# Power.net
KiCad netlist of a schematic drawn in Altium Designer
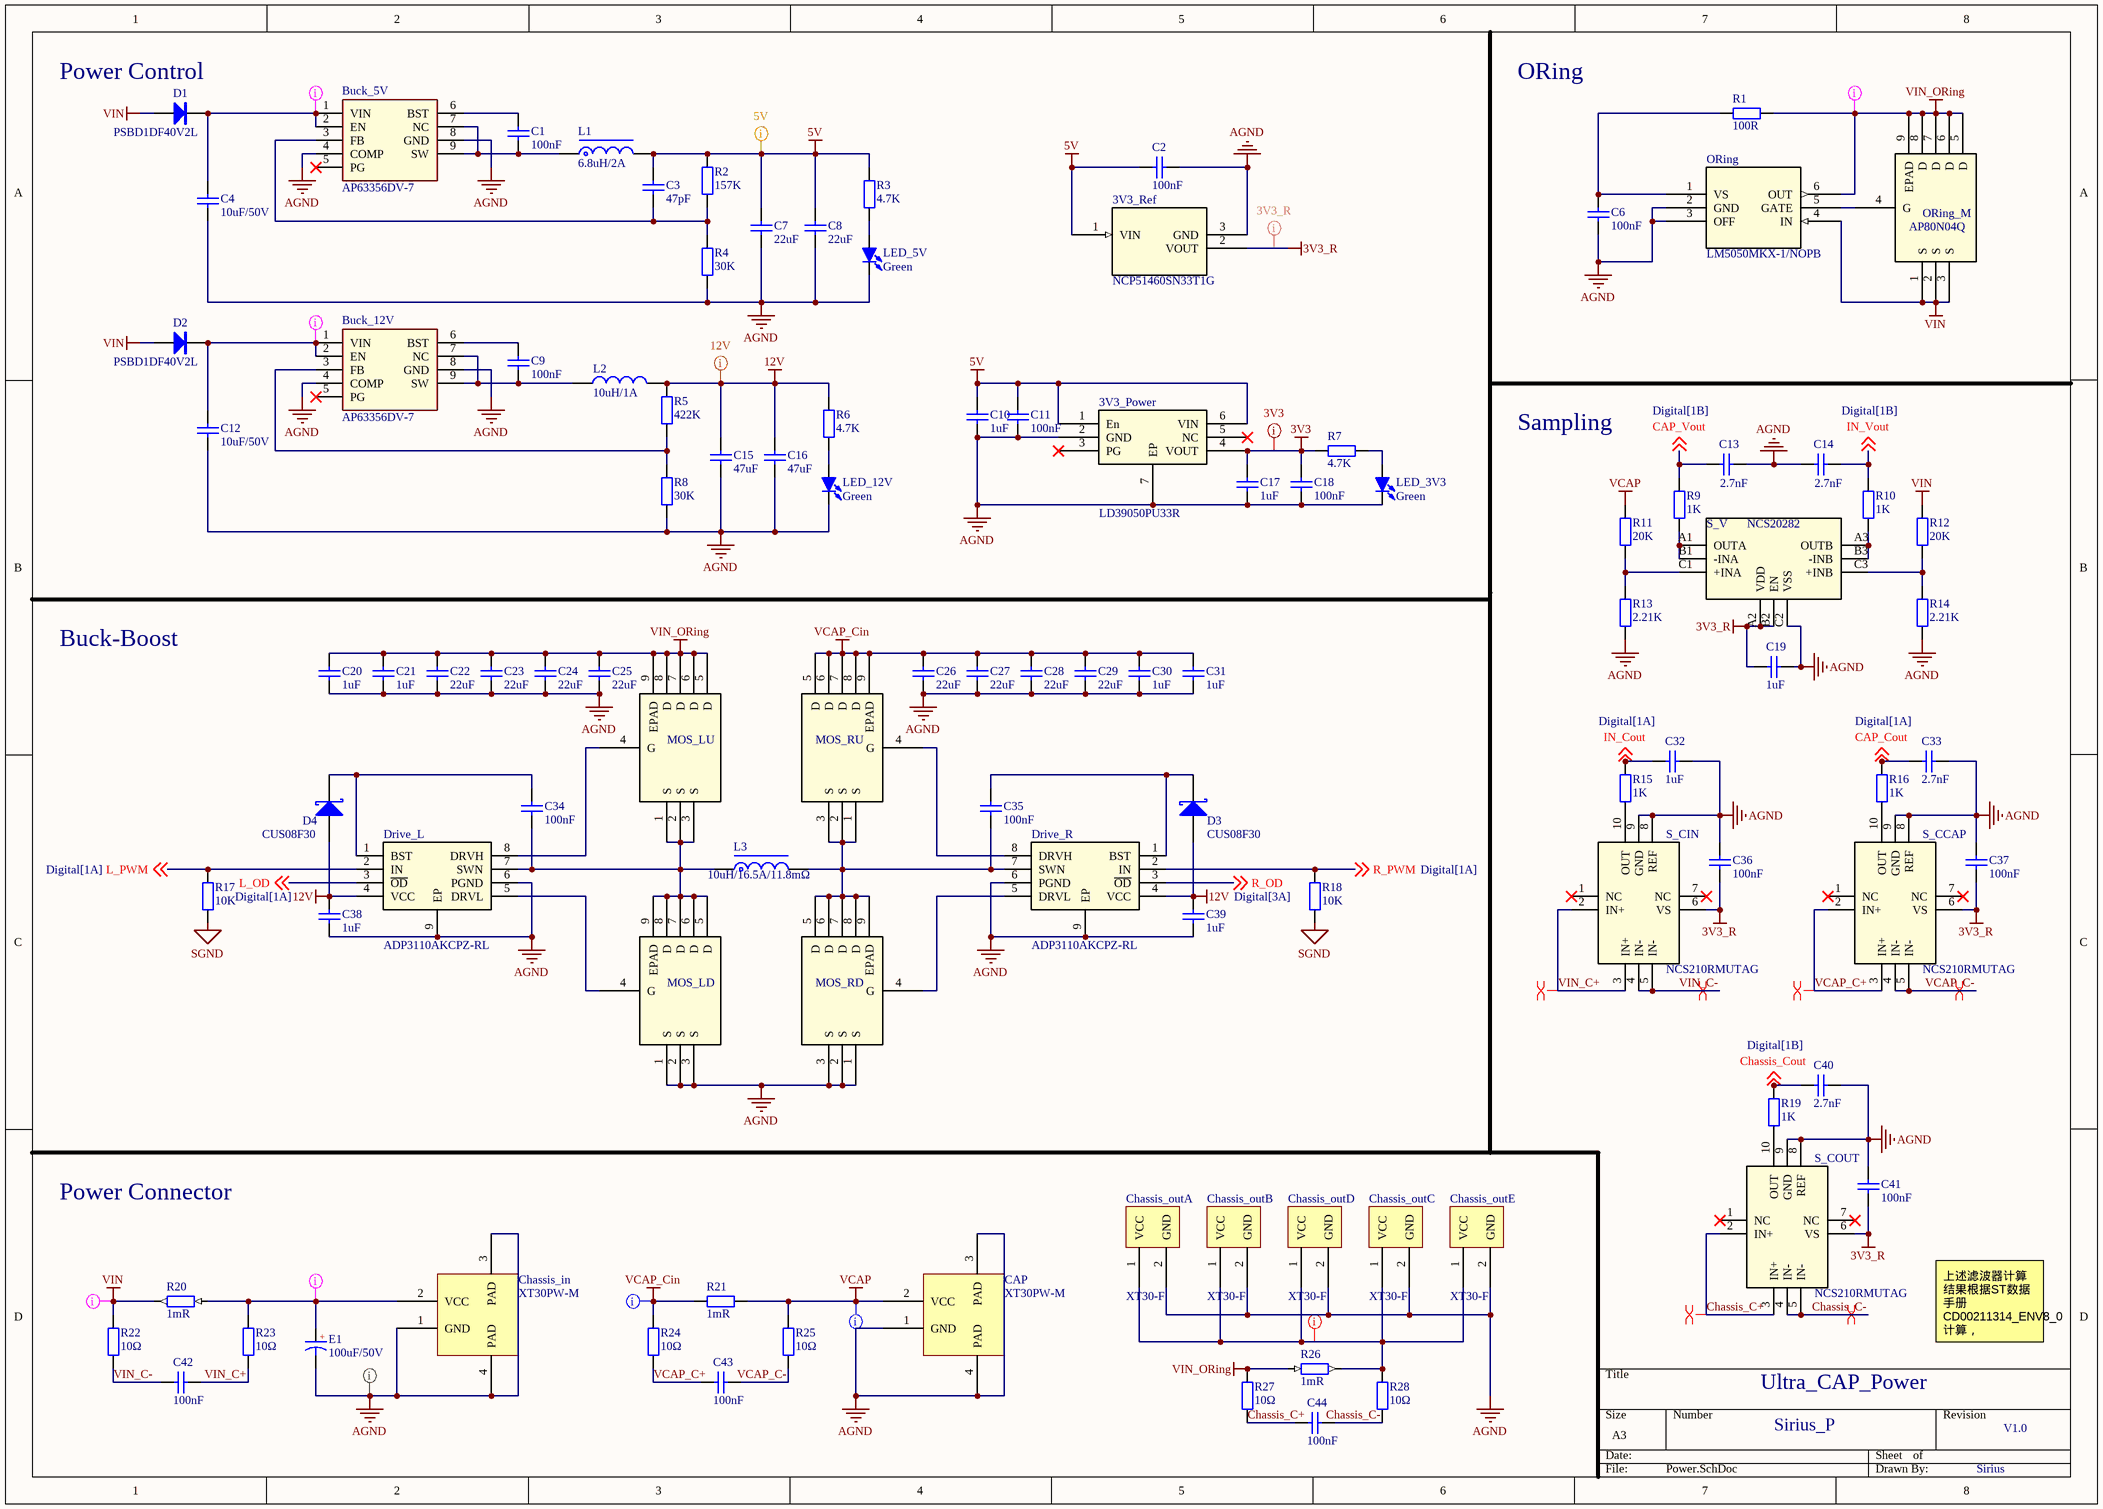
[diagram p0: Power.SchDoc]

(export (version "E")
  (design (tool "Eeschema 10.0.6"))
  (components
    (comp (ref "3V3_Power")
      (value "LD39050PU33R")
      (footprint "SON_DFN6_3X3_STM-L")
      (description "LDO-3V3/500mA")
      (libsource (lib "Extra Sch") (part "LD39050PU33R"))
    )
    (comp (ref "3V3_Ref")
      (value "NCP51460SN33T1G")
      (footprint "SOT23")
      (description "基准电压源3V3")
      (fields (field (name "COPYRIGHT") "Copyright (C) 2022 Ultra Librarian. All rights reserved."))
      (libsource (lib "Extra Sch") (part "NCP51460SN33T1G"))
    )
    (comp (ref "Buck_5V")
      (value "AP63356DV-7")
      (footprint "AP63356DV7")
      (fields (field (name "MOUSER PART NUMBER") "621-AP63356DV-7"))
      (libsource (lib "Extra Sch") (part "AP63356DV-7"))
    )
    (comp (ref "Buck_12V")
      (value "AP63356DV-7")
      (footprint "AP63356DV7")
      (fields (field (name "MOUSER PART NUMBER") "621-AP63356DV-7"))
      (libsource (lib "Extra Sch") (part "AP63356DV-7"))
    )
    (comp (ref "C1")
      (value "100nF")
      (footprint "C0603_L")
      (description "贴片电容")
      (libsource (lib "0.1 - 电阻-电容-电感-晶振-晶体-磁珠-电位器") (part "C"))
    )
    (comp (ref "C2")
      (value "100nF")
      (footprint "C0603_L")
      (description "贴片电容")
      (libsource (lib "0.1 - 电阻-电容-电感-晶振-晶体-磁珠-电位器") (part "C"))
    )
    (comp (ref "C3")
      (value "47pF")
      (footprint "C0603_L")
      (description "贴片电容")
      (libsource (lib "0.1 - 电阻-电容-电感-晶振-晶体-磁珠-电位器") (part "C"))
    )
    (comp (ref "C4")
      (value "10uF/50V")
      (footprint "C0603_L")
      (description "贴片电容")
      (libsource (lib "0.1 - 电阻-电容-电感-晶振-晶体-磁珠-电位器") (part "C"))
    )
    (comp (ref "C6")
      (value "100nF")
      (footprint "C0603_L")
      (description "贴片电容")
      (libsource (lib "0.1 - 电阻-电容-电感-晶振-晶体-磁珠-电位器") (part "C"))
    )
    (comp (ref "C7")
      (value "22uF")
      (footprint "C1210_L")
      (description "贴片电容")
      (libsource (lib "0.1 - 电阻-电容-电感-晶振-晶体-磁珠-电位器") (part "C"))
    )
    (comp (ref "C8")
      (value "22uF")
      (footprint "C1210_L")
      (description "贴片电容")
      (libsource (lib "0.1 - 电阻-电容-电感-晶振-晶体-磁珠-电位器") (part "C"))
    )
    (comp (ref "C9")
      (value "100nF")
      (footprint "C0603_L")
      (description "贴片电容")
      (libsource (lib "0.1 - 电阻-电容-电感-晶振-晶体-磁珠-电位器") (part "C"))
    )
    (comp (ref "C10")
      (value "1uF")
      (footprint "C0603_L")
      (description "贴片电容")
      (libsource (lib "0.1 - 电阻-电容-电感-晶振-晶体-磁珠-电位器") (part "C"))
    )
    (comp (ref "C11")
      (value "100nF")
      (footprint "C0603_L")
      (description "贴片电容")
      (libsource (lib "0.1 - 电阻-电容-电感-晶振-晶体-磁珠-电位器") (part "C"))
    )
    (comp (ref "C12")
      (value "10uF/50V")
      (footprint "C0603_L")
      (description "贴片电容")
      (libsource (lib "0.1 - 电阻-电容-电感-晶振-晶体-磁珠-电位器") (part "C"))
    )
    (comp (ref "C13")
      (value "2.7nF")
      (footprint "C0603_L")
      (description "贴片电容")
      (libsource (lib "0.1 - 电阻-电容-电感-晶振-晶体-磁珠-电位器") (part "C"))
    )
    (comp (ref "C14")
      (value "2.7nF")
      (footprint "C0603_L")
      (description "贴片电容")
      (libsource (lib "0.1 - 电阻-电容-电感-晶振-晶体-磁珠-电位器") (part "C"))
    )
    (comp (ref "C15")
      (value "47uF")
      (footprint "C1206_L")
      (description "贴片电容")
      (libsource (lib "0.1 - 电阻-电容-电感-晶振-晶体-磁珠-电位器") (part "C"))
    )
    (comp (ref "C16")
      (value "47uF")
      (footprint "C1206_L")
      (description "贴片电容")
      (libsource (lib "0.1 - 电阻-电容-电感-晶振-晶体-磁珠-电位器") (part "C"))
    )
    (comp (ref "C17")
      (value "1uF")
      (footprint "C0603_L")
      (description "贴片电容")
      (libsource (lib "0.1 - 电阻-电容-电感-晶振-晶体-磁珠-电位器") (part "C"))
    )
    (comp (ref "C18")
      (value "100nF")
      (footprint "C0603_L")
      (description "贴片电容")
      (libsource (lib "0.1 - 电阻-电容-电感-晶振-晶体-磁珠-电位器") (part "C"))
    )
    (comp (ref "C19")
      (value "1uF")
      (footprint "C0603_L")
      (description "贴片电容")
      (libsource (lib "0.1 - 电阻-电容-电感-晶振-晶体-磁珠-电位器") (part "C"))
    )
    (comp (ref "C20")
      (value "1uF")
      (footprint "C0603_L")
      (description "贴片电容")
      (libsource (lib "0.1 - 电阻-电容-电感-晶振-晶体-磁珠-电位器") (part "C"))
    )
    (comp (ref "C21")
      (value "1uF")
      (footprint "C0603_L")
      (description "贴片电容")
      (libsource (lib "0.1 - 电阻-电容-电感-晶振-晶体-磁珠-电位器") (part "C"))
    )
    (comp (ref "C22")
      (value "22uF")
      (footprint "C2220_no overlay")
      (description "贴片电容")
      (libsource (lib "0.1 - 电阻-电容-电感-晶振-晶体-磁珠-电位器") (part "C"))
    )
    (comp (ref "C23")
      (value "22uF")
      (footprint "C2220_no overlay")
      (description "贴片电容")
      (libsource (lib "0.1 - 电阻-电容-电感-晶振-晶体-磁珠-电位器") (part "C"))
    )
    (comp (ref "C24")
      (value "22uF")
      (footprint "C2220_no overlay")
      (description "贴片电容")
      (libsource (lib "0.1 - 电阻-电容-电感-晶振-晶体-磁珠-电位器") (part "C"))
    )
    (comp (ref "C25")
      (value "22uF")
      (footprint "C2220_no overlay")
      (description "贴片电容")
      (libsource (lib "0.1 - 电阻-电容-电感-晶振-晶体-磁珠-电位器") (part "C"))
    )
    (comp (ref "C26")
      (value "22uF")
      (footprint "C2220_no overlay")
      (description "贴片电容")
      (libsource (lib "0.1 - 电阻-电容-电感-晶振-晶体-磁珠-电位器") (part "C"))
    )
    (comp (ref "C27")
      (value "22uF")
      (footprint "C2220_no overlay")
      (description "贴片电容")
      (libsource (lib "0.1 - 电阻-电容-电感-晶振-晶体-磁珠-电位器") (part "C"))
    )
    (comp (ref "C28")
      (value "22uF")
      (footprint "C2220_no overlay")
      (description "贴片电容")
      (libsource (lib "0.1 - 电阻-电容-电感-晶振-晶体-磁珠-电位器") (part "C"))
    )
    (comp (ref "C29")
      (value "22uF")
      (footprint "C2220_no overlay")
      (description "贴片电容")
      (libsource (lib "0.1 - 电阻-电容-电感-晶振-晶体-磁珠-电位器") (part "C"))
    )
    (comp (ref "C30")
      (value "1uF")
      (footprint "C0603_L")
      (description "贴片电容")
      (libsource (lib "0.1 - 电阻-电容-电感-晶振-晶体-磁珠-电位器") (part "C"))
    )
    (comp (ref "C31")
      (value "1uF")
      (footprint "C0603_L")
      (description "贴片电容")
      (libsource (lib "0.1 - 电阻-电容-电感-晶振-晶体-磁珠-电位器") (part "C"))
    )
    (comp (ref "C32")
      (value "1uF")
      (footprint "C0603_L")
      (description "贴片电容")
      (libsource (lib "0.1 - 电阻-电容-电感-晶振-晶体-磁珠-电位器") (part "C"))
    )
    (comp (ref "C33")
      (value "2.7nF")
      (footprint "C0603_L")
      (description "贴片电容")
      (libsource (lib "0.1 - 电阻-电容-电感-晶振-晶体-磁珠-电位器") (part "C"))
    )
    (comp (ref "C34")
      (value "100nF")
      (footprint "C0603_L")
      (description "贴片电容")
      (libsource (lib "0.1 - 电阻-电容-电感-晶振-晶体-磁珠-电位器") (part "C"))
    )
    (comp (ref "C35")
      (value "100nF")
      (footprint "C0603_L")
      (description "贴片电容")
      (libsource (lib "0.1 - 电阻-电容-电感-晶振-晶体-磁珠-电位器") (part "C"))
    )
    (comp (ref "C36")
      (value "100nF")
      (footprint "C0603_L")
      (description "贴片电容")
      (libsource (lib "0.1 - 电阻-电容-电感-晶振-晶体-磁珠-电位器") (part "C"))
    )
    (comp (ref "C37")
      (value "100nF")
      (footprint "C0603_L")
      (description "贴片电容")
      (libsource (lib "0.1 - 电阻-电容-电感-晶振-晶体-磁珠-电位器") (part "C"))
    )
    (comp (ref "C38")
      (value "1uF")
      (footprint "C0603_L")
      (description "贴片电容")
      (libsource (lib "0.1 - 电阻-电容-电感-晶振-晶体-磁珠-电位器") (part "C"))
    )
    (comp (ref "C39")
      (value "1uF")
      (footprint "C0603_L")
      (description "贴片电容")
      (libsource (lib "0.1 - 电阻-电容-电感-晶振-晶体-磁珠-电位器") (part "C"))
    )
    (comp (ref "C40")
      (value "2.7nF")
      (footprint "C0603_L")
      (description "贴片电容")
      (libsource (lib "0.1 - 电阻-电容-电感-晶振-晶体-磁珠-电位器") (part "C"))
    )
    (comp (ref "C41")
      (value "100nF")
      (footprint "C0603_L")
      (description "贴片电容")
      (libsource (lib "0.1 - 电阻-电容-电感-晶振-晶体-磁珠-电位器") (part "C"))
    )
    (comp (ref "C42")
      (value "100nF")
      (footprint "C0603_L")
      (description "贴片电容")
      (libsource (lib "0.1 - 电阻-电容-电感-晶振-晶体-磁珠-电位器") (part "C"))
    )
    (comp (ref "C43")
      (value "100nF")
      (footprint "C0603_L")
      (description "贴片电容")
      (libsource (lib "0.1 - 电阻-电容-电感-晶振-晶体-磁珠-电位器") (part "C"))
    )
    (comp (ref "C44")
      (value "100nF")
      (footprint "C0603_L")
      (description "贴片电容")
      (libsource (lib "0.1 - 电阻-电容-电感-晶振-晶体-磁珠-电位器") (part "C"))
    )
    (comp (ref "CAP")
      (value "XT30PW-M")
      (footprint "CONN-TH_XT30PW-M")
      (libsource (lib "Extra Sch") (part "XT30PW-M"))
    )
    (comp (ref "Chassis_in")
      (value "XT30PW-M")
      (footprint "CONN-TH_XT30PW-M")
      (libsource (lib "Extra Sch") (part "XT30PW-M"))
    )
    (comp (ref "Chassis_outA")
      (value "XT30-F")
      (footprint "XT30-F")
      (libsource (lib "Extra Sch") (part "XT30-F"))
    )
    (comp (ref "Chassis_outB")
      (value "XT30-F")
      (footprint "XT30-F")
      (libsource (lib "Extra Sch") (part "XT30-F"))
    )
    (comp (ref "Chassis_outC")
      (value "XT30-F")
      (footprint "XT30-F")
      (libsource (lib "Extra Sch") (part "XT30-F"))
    )
    (comp (ref "Chassis_outD")
      (value "XT30-F")
      (footprint "XT30-F")
      (libsource (lib "Extra Sch") (part "XT30-F"))
    )
    (comp (ref "Chassis_outE")
      (value "XT30-F")
      (footprint "XT30-F")
      (libsource (lib "Extra Sch") (part "XT30-F"))
    )
    (comp (ref "D1")
      (value "PSBD1DF40V2L")
      (footprint "SOD-123")
      (description "肖特基二极管")
      (libsource (lib "0.2 - 二极管-TVS-ESD-整流桥") (part "1N5822"))
    )
    (comp (ref "D2")
      (value "PSBD1DF40V2L")
      (footprint "SOD-123")
      (description "肖特基二极管")
      (libsource (lib "0.2 - 二极管-TVS-ESD-整流桥") (part "1N5822"))
    )
    (comp (ref "D3")
      (value "CUS08F30")
      (footprint "SOD-323")
      (description "肖特基二极管")
      (libsource (lib "0.2 - 二极管-TVS-ESD-整流桥") (part "1N5819"))
    )
    (comp (ref "D4")
      (value "CUS08F30")
      (footprint "SOD-323")
      (description "肖特基二极管")
      (libsource (lib "0.2 - 二极管-TVS-ESD-整流桥") (part "1N5819"))
    )
    (comp (ref "Drive_L")
      (value "ADP3110AKCPZ-RL")
      (footprint "SON50P300X300X100-9N")
      (fields (field (name "MOUSER PART NUMBER") "863-ADP3110AKCPZ-RL"))
      (libsource (lib "") (part "ADP3110AKCPZ-RL_1"))
    )
    (comp (ref "Drive_R")
      (value "ADP3110AKCPZ-RL")
      (footprint "SON50P300X300X100-9N")
      (fields (field (name "MOUSER PART NUMBER") "863-ADP3110AKCPZ-RL"))
      (libsource (lib "Extra Sch") (part "ADP3110AKCPZ-RL"))
    )
    (comp (ref "E1")
      (value "100uF/50V")
      (footprint "CT 3.5*8*8 - R")
      (description "直插固态电容")
      (libsource (lib "0.1 - 电阻-电容-电感-晶振-晶体-磁珠-电位器") (part "CS"))
    )
    (comp (ref "L1")
      (value "6.8uH/2A")
      (footprint "L-SMD-0420")
      (description "一体成型电感")
      (libsource (lib "0.1 - 电阻-电容-电感-晶振-晶体-磁珠-电位器") (part "L-Molding Choke"))
    )
    (comp (ref "L2")
      (value "10uH/1A")
      (footprint "L1210")
      (description "贴片小功率电感")
      (libsource (lib "0.1 - 电阻-电容-电感-晶振-晶体-磁珠-电位器") (part "L"))
    )
    (comp (ref "L3")
      (value "10uH/16.5A/11.8mΩ")
      (footprint "INDPM176169X700N")
      (description "一体成型电感\r\nTMPC1707HP-100MG-D")
      (libsource (lib "0.1 - 电阻-电容-电感-晶振-晶体-磁珠-电位器") (part "L-Molding Choke"))
    )
    (comp (ref "LED_3V3")
      (value "Green")
      (footprint "LED0603_G")
      (description "贴片LED")
      (libsource (lib "0.3 - LED发光二极管-IR二极管_接收管-光耦") (part "LED-SMD"))
    )
    (comp (ref "LED_5V")
      (value "Green")
      (footprint "LED0603_G")
      (description "贴片LED")
      (libsource (lib "0.3 - LED发光二极管-IR二极管_接收管-光耦") (part "LED-SMD"))
    )
    (comp (ref "LED_12V")
      (value "Green")
      (footprint "LED0603_G")
      (description "贴片LED")
      (libsource (lib "0.3 - LED发光二极管-IR二极管_接收管-光耦") (part "LED-SMD"))
    )
    (comp (ref "MOS_LD")
      (value "HYG025N06LS1C2")
      (footprint "PDFN5*6-8l")
      (description "NMOS 60V/170A")
      (fields
        (field (name "MANUFACTURER_PART_NUMBER") "AON7418")
        (field (name "COPYRIGHT") "Copyright (C) 2022 Ultra Librarian. All rights reserved.")
      )
      (libsource (lib "") (part "HYG025N06LS1C2_1"))
    )
    (comp (ref "MOS_LU")
      (value "HYG025N06LS1C2")
      (footprint "PDFN5*6-8l")
      (description "NMOS 60V/170A")
      (fields
        (field (name "MANUFACTURER_PART_NUMBER") "AON7418")
        (field (name "COPYRIGHT") "Copyright (C) 2022 Ultra Librarian. All rights reserved.")
      )
      (libsource (lib "") (part "HYG025N06LS1C2_1"))
    )
    (comp (ref "MOS_RD")
      (value "HYG025N06LS1C2")
      (footprint "PDFN5*6-8l")
      (description "NMOS 60V/170A")
      (fields
        (field (name "MANUFACTURER_PART_NUMBER") "AON7418")
        (field (name "COPYRIGHT") "Copyright (C) 2022 Ultra Librarian. All rights reserved.")
      )
      (libsource (lib "Extra Sch") (part "HYG025N06LS1C2"))
    )
    (comp (ref "MOS_RU")
      (value "HYG025N06LS1C2")
      (footprint "PDFN5*6-8l")
      (description "NMOS 60V/170A")
      (fields
        (field (name "MANUFACTURER_PART_NUMBER") "AON7418")
        (field (name "COPYRIGHT") "Copyright (C) 2022 Ultra Librarian. All rights reserved.")
      )
      (libsource (lib "Extra Sch") (part "HYG025N06LS1C2"))
    )
    (comp (ref "ORing")
      (value "LM5050MKX-1/NOPB")
      (footprint "SOT23-6")
      (description "理想二极管控制器")
      (fields (field (name "COPYRIGHT") "Copyright (C) 2022 Ultra Librarian. All rights reserved."))
      (libsource (lib "Extra Sch") (part "LM5050MKX-1/NOPB"))
    )
    (comp (ref "ORing_M")
      (value "AP80N04Q")
      (footprint "TDFN33-8")
      (description "Trans MOSFET N-CH 40V 40A 8-Pin PDFN EP T/R")
      (fields
        (field (name "MANUFACTURER_PART_NUMBER") "TSM085P03CV RGG")
        (field (name "MOUSER PART NUMBER") "821-TSM085P03CVRGG")
      )
      (libsource (lib "Extra Sch") (part "AP80N04Q"))
    )
    (comp (ref "R1")
      (value "100R")
      (footprint "R0603_L")
      (description "贴片电阻")
      (libsource (lib "0.1 - 电阻-电容-电感-晶振-晶体-磁珠-电位器") (part "R"))
    )
    (comp (ref "R2")
      (value "157K")
      (footprint "R0603_L")
      (description "贴片电阻")
      (libsource (lib "0.1 - 电阻-电容-电感-晶振-晶体-磁珠-电位器") (part "R"))
    )
    (comp (ref "R3")
      (value "4.7K")
      (footprint "R0603_L")
      (description "贴片电阻")
      (libsource (lib "0.1 - 电阻-电容-电感-晶振-晶体-磁珠-电位器") (part "R"))
    )
    (comp (ref "R4")
      (value "30K")
      (footprint "R0603_L")
      (description "贴片电阻")
      (libsource (lib "0.1 - 电阻-电容-电感-晶振-晶体-磁珠-电位器") (part "R"))
    )
    (comp (ref "R5")
      (value "422K")
      (footprint "R0603_L")
      (description "贴片电阻")
      (libsource (lib "0.1 - 电阻-电容-电感-晶振-晶体-磁珠-电位器") (part "R"))
    )
    (comp (ref "R6")
      (value "4.7K")
      (footprint "R0603_L")
      (description "贴片电阻")
      (libsource (lib "0.1 - 电阻-电容-电感-晶振-晶体-磁珠-电位器") (part "R"))
    )
    (comp (ref "R7")
      (value "4.7K")
      (footprint "R0603_L")
      (description "贴片电阻")
      (libsource (lib "0.1 - 电阻-电容-电感-晶振-晶体-磁珠-电位器") (part "R"))
    )
    (comp (ref "R8")
      (value "30K")
      (footprint "R0603_L")
      (description "贴片电阻")
      (libsource (lib "0.1 - 电阻-电容-电感-晶振-晶体-磁珠-电位器") (part "R"))
    )
    (comp (ref "R9")
      (value "1K")
      (footprint "R0603_L")
      (description "贴片电阻")
      (libsource (lib "0.1 - 电阻-电容-电感-晶振-晶体-磁珠-电位器") (part "R"))
    )
    (comp (ref "R10")
      (value "1K")
      (footprint "R0603_L")
      (description "贴片电阻")
      (libsource (lib "0.1 - 电阻-电容-电感-晶振-晶体-磁珠-电位器") (part "R"))
    )
    (comp (ref "R11")
      (value "20K")
      (footprint "R0603_L")
      (description "贴片电阻")
      (libsource (lib "0.1 - 电阻-电容-电感-晶振-晶体-磁珠-电位器") (part "R"))
    )
    (comp (ref "R12")
      (value "20K")
      (footprint "R0603_L")
      (description "贴片电阻")
      (libsource (lib "0.1 - 电阻-电容-电感-晶振-晶体-磁珠-电位器") (part "R"))
    )
    (comp (ref "R13")
      (value "2.21K")
      (footprint "R0603_L")
      (description "贴片电阻")
      (libsource (lib "0.1 - 电阻-电容-电感-晶振-晶体-磁珠-电位器") (part "R"))
    )
    (comp (ref "R14")
      (value "2.21K")
      (footprint "R0603_L")
      (description "贴片电阻")
      (libsource (lib "0.1 - 电阻-电容-电感-晶振-晶体-磁珠-电位器") (part "R"))
    )
    (comp (ref "R15")
      (value "1K")
      (footprint "R0603_L")
      (description "贴片电阻")
      (libsource (lib "0.1 - 电阻-电容-电感-晶振-晶体-磁珠-电位器") (part "R"))
    )
    (comp (ref "R16")
      (value "1K")
      (footprint "R0603_L")
      (description "贴片电阻")
      (libsource (lib "0.1 - 电阻-电容-电感-晶振-晶体-磁珠-电位器") (part "R"))
    )
    (comp (ref "R17")
      (value "10K")
      (footprint "R0603_L")
      (description "贴片电阻")
      (libsource (lib "0.1 - 电阻-电容-电感-晶振-晶体-磁珠-电位器") (part "R"))
    )
    (comp (ref "R18")
      (value "10K")
      (footprint "R0603_L")
      (description "贴片电阻")
      (libsource (lib "0.1 - 电阻-电容-电感-晶振-晶体-磁珠-电位器") (part "R"))
    )
    (comp (ref "R19")
      (value "1K")
      (footprint "R0603_L")
      (description "贴片电阻")
      (libsource (lib "0.1 - 电阻-电容-电感-晶振-晶体-磁珠-电位器") (part "R"))
    )
    (comp (ref "R20")
      (value "1mR")
      (footprint "R2512_L")
      (description "贴片电阻")
      (libsource (lib "") (part "R_1"))
    )
    (comp (ref "R21")
      (value "1mR")
      (footprint "R2512_L")
      (description "贴片电阻")
      (libsource (lib "") (part "R_2"))
    )
    (comp (ref "R22")
      (value "10Ω")
      (footprint "R0603_L")
      (description "贴片电阻")
      (libsource (lib "0.1 - 电阻-电容-电感-晶振-晶体-磁珠-电位器") (part "R"))
    )
    (comp (ref "R23")
      (value "10Ω")
      (footprint "R0603_L")
      (description "贴片电阻")
      (libsource (lib "0.1 - 电阻-电容-电感-晶振-晶体-磁珠-电位器") (part "R"))
    )
    (comp (ref "R24")
      (value "10Ω")
      (footprint "R0603_L")
      (description "贴片电阻")
      (libsource (lib "0.1 - 电阻-电容-电感-晶振-晶体-磁珠-电位器") (part "R"))
    )
    (comp (ref "R25")
      (value "10Ω")
      (footprint "R0603_L")
      (description "贴片电阻")
      (libsource (lib "0.1 - 电阻-电容-电感-晶振-晶体-磁珠-电位器") (part "R"))
    )
    (comp (ref "R26")
      (value "1mR")
      (footprint "R2512_L")
      (description "贴片电阻")
      (libsource (lib "") (part "R_3"))
    )
    (comp (ref "R27")
      (value "10Ω")
      (footprint "R0603_L")
      (description "贴片电阻")
      (libsource (lib "0.1 - 电阻-电容-电感-晶振-晶体-磁珠-电位器") (part "R"))
    )
    (comp (ref "R28")
      (value "10Ω")
      (footprint "R0603_L")
      (description "贴片电阻")
      (libsource (lib "0.1 - 电阻-电容-电感-晶振-晶体-磁珠-电位器") (part "R"))
    )
    (comp (ref "S_CCAP")
      (value "NCS210RMUTAG")
      (footprint "QFN40P140X180X60-10N")
      (description "CURRENT SENSE AMP G=200")
      (fields (field (name "MOUSER PART NUMBER") "863-NCS210RMUTAG"))
      (libsource (lib "Extra Sch") (part "NCS210RMUTAG"))
    )
    (comp (ref "S_CIN")
      (value "NCS210RMUTAG")
      (footprint "QFN40P140X180X60-10N")
      (description "CURRENT SENSE AMP G=200")
      (fields (field (name "MOUSER PART NUMBER") "863-NCS210RMUTAG"))
      (libsource (lib "Extra Sch") (part "NCS210RMUTAG"))
    )
    (comp (ref "S_COUT")
      (value "NCS210RMUTAG")
      (footprint "QFN40P140X180X60-10N")
      (description "CURRENT SENSE AMP G=200")
      (fields (field (name "MOUSER PART NUMBER") "863-NCS210RMUTAG"))
      (libsource (lib "Extra Sch") (part "NCS210RMUTAG"))
    )
    (comp (ref "S_V")
      (value "NCS20282")
      (footprint "BGA9C40P3X3_122X122X62")
      (description "7 MHz, 125 A Low Power Operational Amplifier")
      (fields
        (field (name "MANUFACTURER_PART_NUMBER") "FAN48610UC50X")
        (field (name "MOUSER PART NUMBER") "512-FAN48610UC50X")
      )
      (libsource (lib "Extra Sch") (part "NCS20282"))
    )
  )
  (nets
    (net (code "2") (name "/Chassis_C+") (class "Default")
      (node (ref "C44") (pin "2") (pinfunction "2_2") (pintype "passive"))
      (node (ref "R27") (pin "2") (pinfunction "2_2") (pintype "passive"))
      (node (ref "S_COUT") (pin "2") (pinfunction "IN+_2") (pintype "passive"))
      (node (ref "S_COUT") (pin "3") (pinfunction "IN+_3") (pintype "passive"))
    )
    (net (code "3") (name "/Chassis_C-") (class "Default")
      (node (ref "C44") (pin "1") (pinfunction "1_1") (pintype "passive"))
      (node (ref "R28") (pin "1") (pinfunction "1_1") (pintype "passive"))
      (node (ref "S_COUT") (pin "4") (pinfunction "IN-_4") (pintype "passive"))
      (node (ref "S_COUT") (pin "5") (pinfunction "IN-_5") (pintype "passive"))
    )
    (net (code "4") (name "/VCAP_C+") (class "Default")
      (node (ref "C43") (pin "2") (pinfunction "2_2") (pintype "passive"))
      (node (ref "R24") (pin "1") (pinfunction "1_1") (pintype "passive"))
      (node (ref "S_CCAP") (pin "2") (pinfunction "IN+_2") (pintype "passive"))
      (node (ref "S_CCAP") (pin "3") (pinfunction "IN+_3") (pintype "passive"))
    )
    (net (code "5") (name "/VCAP_C-") (class "Default")
      (node (ref "C43") (pin "1") (pinfunction "1_1") (pintype "passive"))
      (node (ref "R25") (pin "1") (pinfunction "1_1") (pintype "passive"))
      (node (ref "S_CCAP") (pin "4") (pinfunction "IN-_4") (pintype "passive"))
      (node (ref "S_CCAP") (pin "5") (pinfunction "IN-_5") (pintype "passive"))
    )
    (net (code "6") (name "/VIN_C+") (class "Default")
      (node (ref "C42") (pin "1") (pinfunction "1_1") (pintype "passive"))
      (node (ref "R23") (pin "1") (pinfunction "1_1") (pintype "passive"))
      (node (ref "S_CIN") (pin "2") (pinfunction "IN+_2") (pintype "passive"))
      (node (ref "S_CIN") (pin "3") (pinfunction "IN+_3") (pintype "passive"))
    )
    (net (code "7") (name "/VIN_C-") (class "Default")
      (node (ref "C42") (pin "2") (pinfunction "2_2") (pintype "passive"))
      (node (ref "R22") (pin "1") (pinfunction "1_1") (pintype "passive"))
      (node (ref "S_CIN") (pin "4") (pinfunction "IN-_4") (pintype "passive"))
      (node (ref "S_CIN") (pin "5") (pinfunction "IN-_5") (pintype "passive"))
    )
    (net (code "8") (name "3V3") (class "Default")
      (node (ref "3V3_Power") (pin "4") (pinfunction "VOUT_4") (pintype "passive"))
      (node (ref "C17") (pin "2") (pinfunction "2_2") (pintype "passive"))
      (node (ref "C18") (pin "2") (pinfunction "2_2") (pintype "passive"))
      (node (ref "R7") (pin "2") (pinfunction "2_2") (pintype "passive"))
    )
    (net (code "9") (name "3V3_R") (class "Default")
      (node (ref "3V3_Ref") (pin "2") (pinfunction "VOUT_2") (pintype "power_in"))
      (node (ref "C19") (pin "2") (pinfunction "2_2") (pintype "passive"))
      (node (ref "C36") (pin "1") (pinfunction "1_1") (pintype "passive"))
      (node (ref "C37") (pin "1") (pinfunction "1_1") (pintype "passive"))
      (node (ref "C41") (pin "1") (pinfunction "1_1") (pintype "passive"))
      (node (ref "S_CCAP") (pin "6") (pinfunction "VS_6") (pintype "passive"))
      (node (ref "S_CIN") (pin "6") (pinfunction "VS_6") (pintype "passive"))
      (node (ref "S_COUT") (pin "6") (pinfunction "VS_6") (pintype "passive"))
      (node (ref "S_V") (pin "A2") (pinfunction "VDD_A2") (pintype "passive"))
      (node (ref "S_V") (pin "B2") (pinfunction "EN_B2") (pintype "passive"))
    )
    (net (code "10") (name "5V") (class "Default")
      (node (ref "3V3_Power") (pin "1") (pinfunction "En_1") (pintype "passive"))
      (node (ref "3V3_Power") (pin "6") (pinfunction "VIN_6") (pintype "passive"))
      (node (ref "3V3_Ref") (pin "1") (pinfunction "VIN_1") (pintype "input"))
      (node (ref "C10") (pin "2") (pinfunction "2_2") (pintype "passive"))
      (node (ref "C11") (pin "2") (pinfunction "2_2") (pintype "passive"))
      (node (ref "C2") (pin "2") (pinfunction "2_2") (pintype "passive"))
      (node (ref "C3") (pin "2") (pinfunction "2_2") (pintype "passive"))
      (node (ref "C7") (pin "2") (pinfunction "2_2") (pintype "passive"))
      (node (ref "C8") (pin "2") (pinfunction "2_2") (pintype "passive"))
      (node (ref "L1") (pin "2") (pinfunction "2_2") (pintype "passive"))
      (node (ref "R2") (pin "2") (pinfunction "2_2") (pintype "passive"))
      (node (ref "R3") (pin "2") (pinfunction "2_2") (pintype "passive"))
    )
    (net (code "11") (name "12V") (class "Default")
      (node (ref "C15") (pin "2") (pinfunction "2_2") (pintype "passive"))
      (node (ref "C16") (pin "2") (pinfunction "2_2") (pintype "passive"))
      (node (ref "C38") (pin "1") (pinfunction "1_1") (pintype "passive"))
      (node (ref "C39") (pin "1") (pinfunction "1_1") (pintype "passive"))
      (node (ref "D3") (pin "1") (pinfunction "A_1") (pintype "passive"))
      (node (ref "D4") (pin "1") (pinfunction "A_1") (pintype "passive"))
      (node (ref "Drive_L") (pin "4") (pinfunction "VCC_4") (pintype "passive"))
      (node (ref "Drive_R") (pin "4") (pinfunction "VCC_4") (pintype "passive"))
      (node (ref "L2") (pin "2") (pinfunction "2_2") (pintype "passive"))
      (node (ref "R5") (pin "2") (pinfunction "2_2") (pintype "passive"))
      (node (ref "R6") (pin "2") (pinfunction "2_2") (pintype "passive"))
    )
    (net (code "12") (name "AGND") (class "Default")
      (node (ref "3V3_Power") (pin "2") (pinfunction "GND_2") (pintype "passive"))
      (node (ref "3V3_Power") (pin "7") (pinfunction "EP_7") (pintype "passive"))
      (node (ref "3V3_Ref") (pin "3") (pinfunction "GND_3") (pintype "power_in"))
      (node (ref "Buck_12V") (pin "4") (pinfunction "COMP_4") (pintype "passive"))
      (node (ref "Buck_12V") (pin "8") (pinfunction "GND_8") (pintype "passive"))
      (node (ref "Buck_5V") (pin "4") (pinfunction "COMP_4") (pintype "passive"))
      (node (ref "Buck_5V") (pin "8") (pinfunction "GND_8") (pintype "passive"))
      (node (ref "C10") (pin "1") (pinfunction "1_1") (pintype "passive"))
      (node (ref "C11") (pin "1") (pinfunction "1_1") (pintype "passive"))
      (node (ref "C12") (pin "1") (pinfunction "1_1") (pintype "passive"))
      (node (ref "C13") (pin "2") (pinfunction "2_2") (pintype "passive"))
      (node (ref "C14") (pin "1") (pinfunction "1_1") (pintype "passive"))
      (node (ref "C15") (pin "1") (pinfunction "1_1") (pintype "passive"))
      (node (ref "C16") (pin "1") (pinfunction "1_1") (pintype "passive"))
      (node (ref "C17") (pin "1") (pinfunction "1_1") (pintype "passive"))
      (node (ref "C18") (pin "1") (pinfunction "1_1") (pintype "passive"))
      (node (ref "C19") (pin "1") (pinfunction "1_1") (pintype "passive"))
      (node (ref "C2") (pin "1") (pinfunction "1_1") (pintype "passive"))
      (node (ref "C20") (pin "1") (pinfunction "1_1") (pintype "passive"))
      (node (ref "C21") (pin "1") (pinfunction "1_1") (pintype "passive"))
      (node (ref "C22") (pin "1") (pinfunction "1_1") (pintype "passive"))
      (node (ref "C23") (pin "1") (pinfunction "1_1") (pintype "passive"))
      (node (ref "C24") (pin "1") (pinfunction "1_1") (pintype "passive"))
      (node (ref "C25") (pin "1") (pinfunction "1_1") (pintype "passive"))
      (node (ref "C26") (pin "1") (pinfunction "1_1") (pintype "passive"))
      (node (ref "C27") (pin "1") (pinfunction "1_1") (pintype "passive"))
      (node (ref "C28") (pin "1") (pinfunction "1_1") (pintype "passive"))
      (node (ref "C29") (pin "1") (pinfunction "1_1") (pintype "passive"))
      (node (ref "C30") (pin "1") (pinfunction "1_1") (pintype "passive"))
      (node (ref "C31") (pin "1") (pinfunction "1_1") (pintype "passive"))
      (node (ref "C32") (pin "2") (pinfunction "2_2") (pintype "passive"))
      (node (ref "C33") (pin "2") (pinfunction "2_2") (pintype "passive"))
      (node (ref "C36") (pin "2") (pinfunction "2_2") (pintype "passive"))
      (node (ref "C37") (pin "2") (pinfunction "2_2") (pintype "passive"))
      (node (ref "C38") (pin "2") (pinfunction "2_2") (pintype "passive"))
      (node (ref "C39") (pin "2") (pinfunction "2_2") (pintype "passive"))
      (node (ref "C4") (pin "1") (pinfunction "1_1") (pintype "passive"))
      (node (ref "C40") (pin "2") (pinfunction "2_2") (pintype "passive"))
      (node (ref "C41") (pin "2") (pinfunction "2_2") (pintype "passive"))
      (node (ref "C6") (pin "1") (pinfunction "1_1") (pintype "passive"))
      (node (ref "C7") (pin "1") (pinfunction "1_1") (pintype "passive"))
      (node (ref "C8") (pin "1") (pinfunction "1_1") (pintype "passive"))
      (node (ref "CAP") (pin "1") (pinfunction "GND_1") (pintype "passive"))
      (node (ref "CAP") (pin "3") (pinfunction "PAD_3") (pintype "passive"))
      (node (ref "CAP") (pin "4") (pinfunction "PAD_4") (pintype "passive"))
      (node (ref "Chassis_in") (pin "1") (pinfunction "GND_1") (pintype "passive"))
      (node (ref "Chassis_in") (pin "3") (pinfunction "PAD_3") (pintype "passive"))
      (node (ref "Chassis_in") (pin "4") (pinfunction "PAD_4") (pintype "passive"))
      (node (ref "Chassis_outA") (pin "2") (pinfunction "GND_2") (pintype "passive"))
      (node (ref "Chassis_outB") (pin "2") (pinfunction "GND_2") (pintype "passive"))
      (node (ref "Chassis_outC") (pin "2") (pinfunction "GND_2") (pintype "passive"))
      (node (ref "Chassis_outD") (pin "2") (pinfunction "GND_2") (pintype "passive"))
      (node (ref "Chassis_outE") (pin "2") (pinfunction "GND_2") (pintype "passive"))
      (node (ref "Drive_L") (pin "6") (pinfunction "PGND_6") (pintype "passive"))
      (node (ref "Drive_L") (pin "9") (pinfunction "EP_9") (pintype "passive"))
      (node (ref "Drive_R") (pin "6") (pinfunction "PGND_6") (pintype "passive"))
      (node (ref "Drive_R") (pin "9") (pinfunction "EP_9") (pintype "passive"))
      (node (ref "E1") (pin "2") (pinfunction "2_2") (pintype "passive"))
      (node (ref "LED_12V") (pin "2") (pinfunction "K_2") (pintype "passive"))
      (node (ref "LED_3V3") (pin "2") (pinfunction "K_2") (pintype "passive"))
      (node (ref "LED_5V") (pin "2") (pinfunction "K_2") (pintype "passive"))
      (node (ref "MOS_LD") (pin "1") (pinfunction "S_1") (pintype "passive"))
      (node (ref "MOS_LD") (pin "2") (pinfunction "S_2") (pintype "passive"))
      (node (ref "MOS_LD") (pin "3") (pinfunction "S_3") (pintype "passive"))
      (node (ref "MOS_RD") (pin "1") (pinfunction "S_1") (pintype "passive"))
      (node (ref "MOS_RD") (pin "2") (pinfunction "S_2") (pintype "passive"))
      (node (ref "MOS_RD") (pin "3") (pinfunction "S_3") (pintype "passive"))
      (node (ref "ORing") (pin "2") (pinfunction "GND_2") (pintype "power_in"))
      (node (ref "ORing") (pin "3") (pinfunction "OFF_3") (pintype "passive"))
      (node (ref "R13") (pin "1") (pinfunction "1_1") (pintype "passive"))
      (node (ref "R14") (pin "1") (pinfunction "1_1") (pintype "passive"))
      (node (ref "R4") (pin "1") (pinfunction "1_1") (pintype "passive"))
      (node (ref "R8") (pin "1") (pinfunction "1_1") (pintype "passive"))
      (node (ref "S_CCAP") (pin "8") (pinfunction "REF_8") (pintype "passive"))
      (node (ref "S_CCAP") (pin "9") (pinfunction "GND_9") (pintype "passive"))
      (node (ref "S_CIN") (pin "8") (pinfunction "REF_8") (pintype "passive"))
      (node (ref "S_CIN") (pin "9") (pinfunction "GND_9") (pintype "passive"))
      (node (ref "S_COUT") (pin "8") (pinfunction "REF_8") (pintype "passive"))
      (node (ref "S_COUT") (pin "9") (pinfunction "GND_9") (pintype "passive"))
      (node (ref "S_V") (pin "C2") (pinfunction "VSS_C2") (pintype "passive"))
    )
    (net (code "13") (name "CAP_Cout") (class "Default")
      (node (ref "C33") (pin "1") (pinfunction "1_1") (pintype "passive"))
      (node (ref "R16") (pin "1") (pinfunction "1_1") (pintype "passive"))
    )
    (net (code "14") (name "CAP_Vout") (class "Default")
      (node (ref "C13") (pin "1") (pinfunction "1_1") (pintype "passive"))
      (node (ref "R9") (pin "1") (pinfunction "1_1") (pintype "passive"))
    )
    (net (code "15") (name "Chassis_Cout") (class "Default")
      (node (ref "C40") (pin "1") (pinfunction "1_1") (pintype "passive"))
      (node (ref "R19") (pin "1") (pinfunction "1_1") (pintype "passive"))
    )
    (net (code "16") (name "IN_Cout") (class "Default")
      (node (ref "C32") (pin "1") (pinfunction "1_1") (pintype "passive"))
      (node (ref "R15") (pin "1") (pinfunction "1_1") (pintype "passive"))
    )
    (net (code "17") (name "IN_Vout") (class "Default")
      (node (ref "C14") (pin "2") (pinfunction "2_2") (pintype "passive"))
      (node (ref "R10") (pin "1") (pinfunction "1_1") (pintype "passive"))
    )
    (net (code "18") (name "L_OD") (class "Default")
      (node (ref "Drive_L") (pin "3") (pinfunction "OD_3") (pintype "passive"))
    )
    (net (code "19") (name "L_PWM") (class "Default")
      (node (ref "Drive_L") (pin "2") (pinfunction "IN_2") (pintype "passive"))
      (node (ref "R17") (pin "1") (pinfunction "1_1") (pintype "passive"))
    )
    (net (code "20") (name "Net-(Buck_5V-BST)") (class "Default")
      (node (ref "Buck_5V") (pin "6") (pinfunction "BST_6") (pintype "passive"))
      (node (ref "C1") (pin "2") (pinfunction "2_2") (pintype "passive"))
    )
    (net (code "21") (name "Net-(Buck_5V-EN)") (class "Default")
      (node (ref "Buck_5V") (pin "1") (pinfunction "VIN_1") (pintype "passive"))
      (node (ref "Buck_5V") (pin "2") (pinfunction "EN_2") (pintype "passive"))
      (node (ref "C4") (pin "2") (pinfunction "2_2") (pintype "passive"))
      (node (ref "D1") (pin "2") (pinfunction "K_2") (pintype "passive"))
    )
    (net (code "22") (name "Net-(Buck_5V-FB)") (class "Default")
      (node (ref "Buck_5V") (pin "3") (pinfunction "FB_3") (pintype "passive"))
      (node (ref "C3") (pin "1") (pinfunction "1_1") (pintype "passive"))
      (node (ref "R2") (pin "1") (pinfunction "1_1") (pintype "passive"))
      (node (ref "R4") (pin "2") (pinfunction "2_2") (pintype "passive"))
    )
    (net (code "23") (name "Net-(Buck_5V-NC)") (class "Default")
      (node (ref "Buck_5V") (pin "7") (pinfunction "NC_7") (pintype "passive"))
      (node (ref "Buck_5V") (pin "9") (pinfunction "SW_9") (pintype "passive"))
      (node (ref "C1") (pin "1") (pinfunction "1_1") (pintype "passive"))
      (node (ref "L1") (pin "1") (pinfunction "1_1") (pintype "passive"))
    )
    (net (code "24") (name "Net-(Buck_12V-BST)") (class "Default")
      (node (ref "Buck_12V") (pin "6") (pinfunction "BST_6") (pintype "passive"))
      (node (ref "C9") (pin "2") (pinfunction "2_2") (pintype "passive"))
    )
    (net (code "25") (name "Net-(Buck_12V-EN)") (class "Default")
      (node (ref "Buck_12V") (pin "1") (pinfunction "VIN_1") (pintype "passive"))
      (node (ref "Buck_12V") (pin "2") (pinfunction "EN_2") (pintype "passive"))
      (node (ref "C12") (pin "2") (pinfunction "2_2") (pintype "passive"))
      (node (ref "D2") (pin "2") (pinfunction "K_2") (pintype "passive"))
    )
    (net (code "26") (name "Net-(Buck_12V-FB)") (class "Default")
      (node (ref "Buck_12V") (pin "3") (pinfunction "FB_3") (pintype "passive"))
      (node (ref "R5") (pin "1") (pinfunction "1_1") (pintype "passive"))
      (node (ref "R8") (pin "2") (pinfunction "2_2") (pintype "passive"))
    )
    (net (code "27") (name "Net-(Buck_12V-NC)") (class "Default")
      (node (ref "Buck_12V") (pin "7") (pinfunction "NC_7") (pintype "passive"))
      (node (ref "Buck_12V") (pin "9") (pinfunction "SW_9") (pintype "passive"))
      (node (ref "C9") (pin "1") (pinfunction "1_1") (pintype "passive"))
      (node (ref "L2") (pin "1") (pinfunction "1_1") (pintype "passive"))
    )
    (net (code "28") (name "Net-(Chassis_in-VCC)") (class "Default")
      (node (ref "Chassis_in") (pin "2") (pinfunction "VCC_2") (pintype "power_in"))
      (node (ref "E1") (pin "1") (pinfunction "1_1") (pintype "passive"))
      (node (ref "R20") (pin "2") (pinfunction "2_2") (pintype "input"))
      (node (ref "R23") (pin "2") (pinfunction "2_2") (pintype "passive"))
    )
    (net (code "29") (name "Net-(Chassis_outA-VCC)") (class "Default")
      (node (ref "Chassis_outA") (pin "1") (pinfunction "VCC_1") (pintype "passive"))
      (node (ref "Chassis_outB") (pin "1") (pinfunction "VCC_1") (pintype "passive"))
      (node (ref "Chassis_outC") (pin "1") (pinfunction "VCC_1") (pintype "passive"))
      (node (ref "Chassis_outD") (pin "1") (pinfunction "VCC_1") (pintype "passive"))
      (node (ref "Chassis_outE") (pin "1") (pinfunction "VCC_1") (pintype "passive"))
      (node (ref "R26") (pin "2") (pinfunction "2_2") (pintype "output"))
      (node (ref "R28") (pin "2") (pinfunction "2_2") (pintype "passive"))
    )
    (net (code "30") (name "Net-(D3-K)") (class "Default")
      (node (ref "C35") (pin "1") (pinfunction "1_1") (pintype "passive"))
      (node (ref "D3") (pin "2") (pinfunction "K_2") (pintype "passive"))
      (node (ref "Drive_R") (pin "1") (pinfunction "BST_1") (pintype "passive"))
    )
    (net (code "31") (name "Net-(D4-K)") (class "Default")
      (node (ref "C34") (pin "1") (pinfunction "1_1") (pintype "passive"))
      (node (ref "D4") (pin "2") (pinfunction "K_2") (pintype "passive"))
      (node (ref "Drive_L") (pin "1") (pinfunction "BST_1") (pintype "passive"))
    )
    (net (code "32") (name "Net-(Drive_L-DRVH)") (class "Default")
      (node (ref "Drive_L") (pin "8") (pinfunction "DRVH_8") (pintype "passive"))
      (node (ref "MOS_LU") (pin "4") (pinfunction "G_4") (pintype "passive"))
    )
    (net (code "33") (name "Net-(Drive_L-DRVL)") (class "Default")
      (node (ref "Drive_L") (pin "5") (pinfunction "DRVL_5") (pintype "passive"))
      (node (ref "MOS_LD") (pin "4") (pinfunction "G_4") (pintype "passive"))
    )
    (net (code "34") (name "Net-(Drive_L-SWN)") (class "Default")
      (node (ref "C34") (pin "2") (pinfunction "2_2") (pintype "passive"))
      (node (ref "Drive_L") (pin "7") (pinfunction "SWN_7") (pintype "passive"))
      (node (ref "L3") (pin "1") (pinfunction "1_1") (pintype "passive"))
      (node (ref "MOS_LD") (pin "5") (pinfunction "D_5") (pintype "passive"))
      (node (ref "MOS_LD") (pin "6") (pinfunction "D_6") (pintype "passive"))
      (node (ref "MOS_LD") (pin "7") (pinfunction "D_7") (pintype "passive"))
      (node (ref "MOS_LD") (pin "8") (pinfunction "D_8") (pintype "passive"))
      (node (ref "MOS_LD") (pin "9") (pinfunction "EPAD_9") (pintype "passive"))
      (node (ref "MOS_LU") (pin "1") (pinfunction "S_1") (pintype "passive"))
      (node (ref "MOS_LU") (pin "2") (pinfunction "S_2") (pintype "passive"))
      (node (ref "MOS_LU") (pin "3") (pinfunction "S_3") (pintype "passive"))
    )
    (net (code "35") (name "Net-(Drive_R-DRVH)") (class "Default")
      (node (ref "Drive_R") (pin "8") (pinfunction "DRVH_8") (pintype "passive"))
      (node (ref "MOS_RU") (pin "4") (pinfunction "G_4") (pintype "passive"))
    )
    (net (code "36") (name "Net-(Drive_R-DRVL)") (class "Default")
      (node (ref "Drive_R") (pin "5") (pinfunction "DRVL_5") (pintype "passive"))
      (node (ref "MOS_RD") (pin "4") (pinfunction "G_4") (pintype "passive"))
    )
    (net (code "37") (name "Net-(Drive_R-SWN)") (class "Default")
      (node (ref "C35") (pin "2") (pinfunction "2_2") (pintype "passive"))
      (node (ref "Drive_R") (pin "7") (pinfunction "SWN_7") (pintype "passive"))
      (node (ref "L3") (pin "2") (pinfunction "2_2") (pintype "passive"))
      (node (ref "MOS_RD") (pin "5") (pinfunction "D_5") (pintype "passive"))
      (node (ref "MOS_RD") (pin "6") (pinfunction "D_6") (pintype "passive"))
      (node (ref "MOS_RD") (pin "7") (pinfunction "D_7") (pintype "passive"))
      (node (ref "MOS_RD") (pin "8") (pinfunction "D_8") (pintype "passive"))
      (node (ref "MOS_RD") (pin "9") (pinfunction "EPAD_9") (pintype "passive"))
      (node (ref "MOS_RU") (pin "1") (pinfunction "S_1") (pintype "passive"))
      (node (ref "MOS_RU") (pin "2") (pinfunction "S_2") (pintype "passive"))
      (node (ref "MOS_RU") (pin "3") (pinfunction "S_3") (pintype "passive"))
    )
    (net (code "38") (name "Net-(LED_3V3-A)") (class "Default")
      (node (ref "LED_3V3") (pin "1") (pinfunction "A_1") (pintype "passive"))
      (node (ref "R7") (pin "1") (pinfunction "1_1") (pintype "passive"))
    )
    (net (code "39") (name "Net-(LED_5V-A)") (class "Default")
      (node (ref "LED_5V") (pin "1") (pinfunction "A_1") (pintype "passive"))
      (node (ref "R3") (pin "1") (pinfunction "1_1") (pintype "passive"))
    )
    (net (code "40") (name "Net-(LED_12V-A)") (class "Default")
      (node (ref "LED_12V") (pin "1") (pinfunction "A_1") (pintype "passive"))
      (node (ref "R6") (pin "1") (pinfunction "1_1") (pintype "passive"))
    )
    (net (code "41") (name "Net-(ORing-GATE)") (class "Default")
      (node (ref "ORing") (pin "5") (pinfunction "GATE_5") (pintype "passive"))
      (node (ref "ORing_M") (pin "4") (pinfunction "G_4") (pintype "passive"))
    )
    (net (code "42") (name "Net-(ORing-VS)") (class "Default")
      (node (ref "C6") (pin "2") (pinfunction "2_2") (pintype "passive"))
      (node (ref "ORing") (pin "1") (pinfunction "VS_1") (pintype "passive"))
      (node (ref "R1") (pin "1") (pinfunction "1_1") (pintype "passive"))
    )
    (net (code "43") (name "Net-(S_CCAP-OUT)") (class "Default")
      (node (ref "R16") (pin "2") (pinfunction "2_2") (pintype "passive"))
      (node (ref "S_CCAP") (pin "10") (pinfunction "OUT_10") (pintype "passive"))
    )
    (net (code "44") (name "Net-(S_CIN-OUT)") (class "Default")
      (node (ref "R15") (pin "2") (pinfunction "2_2") (pintype "passive"))
      (node (ref "S_CIN") (pin "10") (pinfunction "OUT_10") (pintype "passive"))
    )
    (net (code "45") (name "Net-(S_COUT-OUT)") (class "Default")
      (node (ref "R19") (pin "2") (pinfunction "2_2") (pintype "passive"))
      (node (ref "S_COUT") (pin "10") (pinfunction "OUT_10") (pintype "passive"))
    )
    (net (code "46") (name "Net-(S_V-+INA)") (class "Default")
      (node (ref "R11") (pin "2") (pinfunction "2_2") (pintype "passive"))
      (node (ref "R13") (pin "2") (pinfunction "2_2") (pintype "passive"))
      (node (ref "S_V") (pin "C1") (pinfunction "+INA_C1") (pintype "passive"))
    )
    (net (code "47") (name "Net-(S_V-+INB)") (class "Default")
      (node (ref "R12") (pin "2") (pinfunction "2_2") (pintype "passive"))
      (node (ref "R14") (pin "2") (pinfunction "2_2") (pintype "passive"))
      (node (ref "S_V") (pin "C3") (pinfunction "+INB_C3") (pintype "passive"))
    )
    (net (code "48") (name "Net-(S_V--INA)") (class "Default")
      (node (ref "R9") (pin "2") (pinfunction "2_2") (pintype "passive"))
      (node (ref "S_V") (pin "A1") (pinfunction "OUTA_A1") (pintype "passive"))
      (node (ref "S_V") (pin "B1") (pinfunction "-INA_B1") (pintype "passive"))
    )
    (net (code "49") (name "Net-(S_V--INB)") (class "Default")
      (node (ref "R10") (pin "2") (pinfunction "2_2") (pintype "passive"))
      (node (ref "S_V") (pin "A3") (pinfunction "OUTB_A3") (pintype "passive"))
      (node (ref "S_V") (pin "B3") (pinfunction "-INB_B3") (pintype "passive"))
    )
    (net (code "50") (name "R_OD") (class "Default")
      (node (ref "Drive_R") (pin "3") (pinfunction "OD_3") (pintype "passive"))
    )
    (net (code "51") (name "R_PWM") (class "Default")
      (node (ref "Drive_R") (pin "2") (pinfunction "IN_2") (pintype "passive"))
      (node (ref "R18") (pin "1") (pinfunction "1_1") (pintype "passive"))
    )
    (net (code "52") (name "SGND") (class "Default")
      (node (ref "R17") (pin "2") (pinfunction "2_2") (pintype "passive"))
      (node (ref "R18") (pin "2") (pinfunction "2_2") (pintype "passive"))
    )
    (net (code "53") (name "VCAP") (class "Default")
      (node (ref "CAP") (pin "2") (pinfunction "VCC_2") (pintype "power_in"))
      (node (ref "R11") (pin "1") (pinfunction "1_1") (pintype "passive"))
      (node (ref "R21") (pin "2") (pinfunction "2_2") (pintype "bidirectional"))
      (node (ref "R25") (pin "2") (pinfunction "2_2") (pintype "passive"))
    )
    (net (code "54") (name "VCAP_Cin") (class "Default")
      (node (ref "C26") (pin "2") (pinfunction "2_2") (pintype "passive"))
      (node (ref "C27") (pin "2") (pinfunction "2_2") (pintype "passive"))
      (node (ref "C28") (pin "2") (pinfunction "2_2") (pintype "passive"))
      (node (ref "C29") (pin "2") (pinfunction "2_2") (pintype "passive"))
      (node (ref "C30") (pin "2") (pinfunction "2_2") (pintype "passive"))
      (node (ref "C31") (pin "2") (pinfunction "2_2") (pintype "passive"))
      (node (ref "MOS_RU") (pin "5") (pinfunction "D_5") (pintype "passive"))
      (node (ref "MOS_RU") (pin "6") (pinfunction "D_6") (pintype "passive"))
      (node (ref "MOS_RU") (pin "7") (pinfunction "D_7") (pintype "passive"))
      (node (ref "MOS_RU") (pin "8") (pinfunction "D_8") (pintype "passive"))
      (node (ref "MOS_RU") (pin "9") (pinfunction "EPAD_9") (pintype "passive"))
      (node (ref "R21") (pin "1") (pinfunction "1_1") (pintype "bidirectional"))
      (node (ref "R24") (pin "2") (pinfunction "2_2") (pintype "passive"))
    )
    (net (code "55") (name "VIN") (class "Default")
      (node (ref "D1") (pin "1") (pinfunction "A_1") (pintype "passive"))
      (node (ref "D2") (pin "1") (pinfunction "A_1") (pintype "passive"))
      (node (ref "ORing") (pin "4") (pinfunction "IN_4") (pintype "input"))
      (node (ref "ORing_M") (pin "1") (pinfunction "S_1") (pintype "passive"))
      (node (ref "ORing_M") (pin "2") (pinfunction "S_2") (pintype "passive"))
      (node (ref "ORing_M") (pin "3") (pinfunction "S_3") (pintype "passive"))
      (node (ref "R12") (pin "1") (pinfunction "1_1") (pintype "passive"))
      (node (ref "R20") (pin "1") (pinfunction "1_1") (pintype "output"))
      (node (ref "R22") (pin "2") (pinfunction "2_2") (pintype "passive"))
    )
    (net (code "56") (name "VIN_ORing") (class "Default")
      (node (ref "C20") (pin "2") (pinfunction "2_2") (pintype "passive"))
      (node (ref "C21") (pin "2") (pinfunction "2_2") (pintype "passive"))
      (node (ref "C22") (pin "2") (pinfunction "2_2") (pintype "passive"))
      (node (ref "C23") (pin "2") (pinfunction "2_2") (pintype "passive"))
      (node (ref "C24") (pin "2") (pinfunction "2_2") (pintype "passive"))
      (node (ref "C25") (pin "2") (pinfunction "2_2") (pintype "passive"))
      (node (ref "MOS_LU") (pin "5") (pinfunction "D_5") (pintype "passive"))
      (node (ref "MOS_LU") (pin "6") (pinfunction "D_6") (pintype "passive"))
      (node (ref "MOS_LU") (pin "7") (pinfunction "D_7") (pintype "passive"))
      (node (ref "MOS_LU") (pin "8") (pinfunction "D_8") (pintype "passive"))
      (node (ref "MOS_LU") (pin "9") (pinfunction "EPAD_9") (pintype "passive"))
      (node (ref "ORing") (pin "6") (pinfunction "OUT_6") (pintype "output"))
      (node (ref "ORing_M") (pin "5") (pinfunction "D_5") (pintype "passive"))
      (node (ref "ORing_M") (pin "6") (pinfunction "D_6") (pintype "passive"))
      (node (ref "ORing_M") (pin "7") (pinfunction "D_7") (pintype "passive"))
      (node (ref "ORing_M") (pin "8") (pinfunction "D_8") (pintype "passive"))
      (node (ref "ORing_M") (pin "9") (pinfunction "EPAD_9") (pintype "passive"))
      (node (ref "R1") (pin "2") (pinfunction "2_2") (pintype "passive"))
      (node (ref "R26") (pin "1") (pinfunction "1_1") (pintype "input"))
      (node (ref "R27") (pin "1") (pinfunction "1_1") (pintype "passive"))
    )
    (net (code "57") (name "unconnected-(3V3_Power-NC-Pad5)") (class "Default")
      (node (ref "3V3_Power") (pin "5") (pinfunction "NC_5") (pintype "passive+no_connect"))
    )
    (net (code "58") (name "unconnected-(3V3_Power-PG-Pad3)") (class "Default")
      (node (ref "3V3_Power") (pin "3") (pinfunction "PG_3") (pintype "passive+no_connect"))
    )
    (net (code "59") (name "unconnected-(Buck_5V-PG-Pad5)") (class "Default")
      (node (ref "Buck_5V") (pin "5") (pinfunction "PG_5") (pintype "passive+no_connect"))
    )
    (net (code "60") (name "unconnected-(Buck_12V-PG-Pad5)") (class "Default")
      (node (ref "Buck_12V") (pin "5") (pinfunction "PG_5") (pintype "passive+no_connect"))
    )
    (net (code "61") (name "unconnected-(S_CCAP-NC-Pad1)") (class "Default")
      (node (ref "S_CCAP") (pin "1") (pinfunction "NC_1") (pintype "passive+no_connect"))
    )
    (net (code "62") (name "unconnected-(S_CCAP-NC-Pad7)") (class "Default")
      (node (ref "S_CCAP") (pin "7") (pinfunction "NC_7") (pintype "passive+no_connect"))
    )
    (net (code "63") (name "unconnected-(S_CIN-NC-Pad1)") (class "Default")
      (node (ref "S_CIN") (pin "1") (pinfunction "NC_1") (pintype "passive+no_connect"))
    )
    (net (code "64") (name "unconnected-(S_CIN-NC-Pad7)") (class "Default")
      (node (ref "S_CIN") (pin "7") (pinfunction "NC_7") (pintype "passive+no_connect"))
    )
    (net (code "65") (name "unconnected-(S_COUT-NC-Pad1)") (class "Default")
      (node (ref "S_COUT") (pin "1") (pinfunction "NC_1") (pintype "passive+no_connect"))
    )
    (net (code "66") (name "unconnected-(S_COUT-NC-Pad7)") (class "Default")
      (node (ref "S_COUT") (pin "7") (pinfunction "NC_7") (pintype "passive+no_connect"))
    )
  )
)
